# S_ANALOG-G5-5A_schDoc.net
KiCad netlist of a schematic drawn in Altium Designer
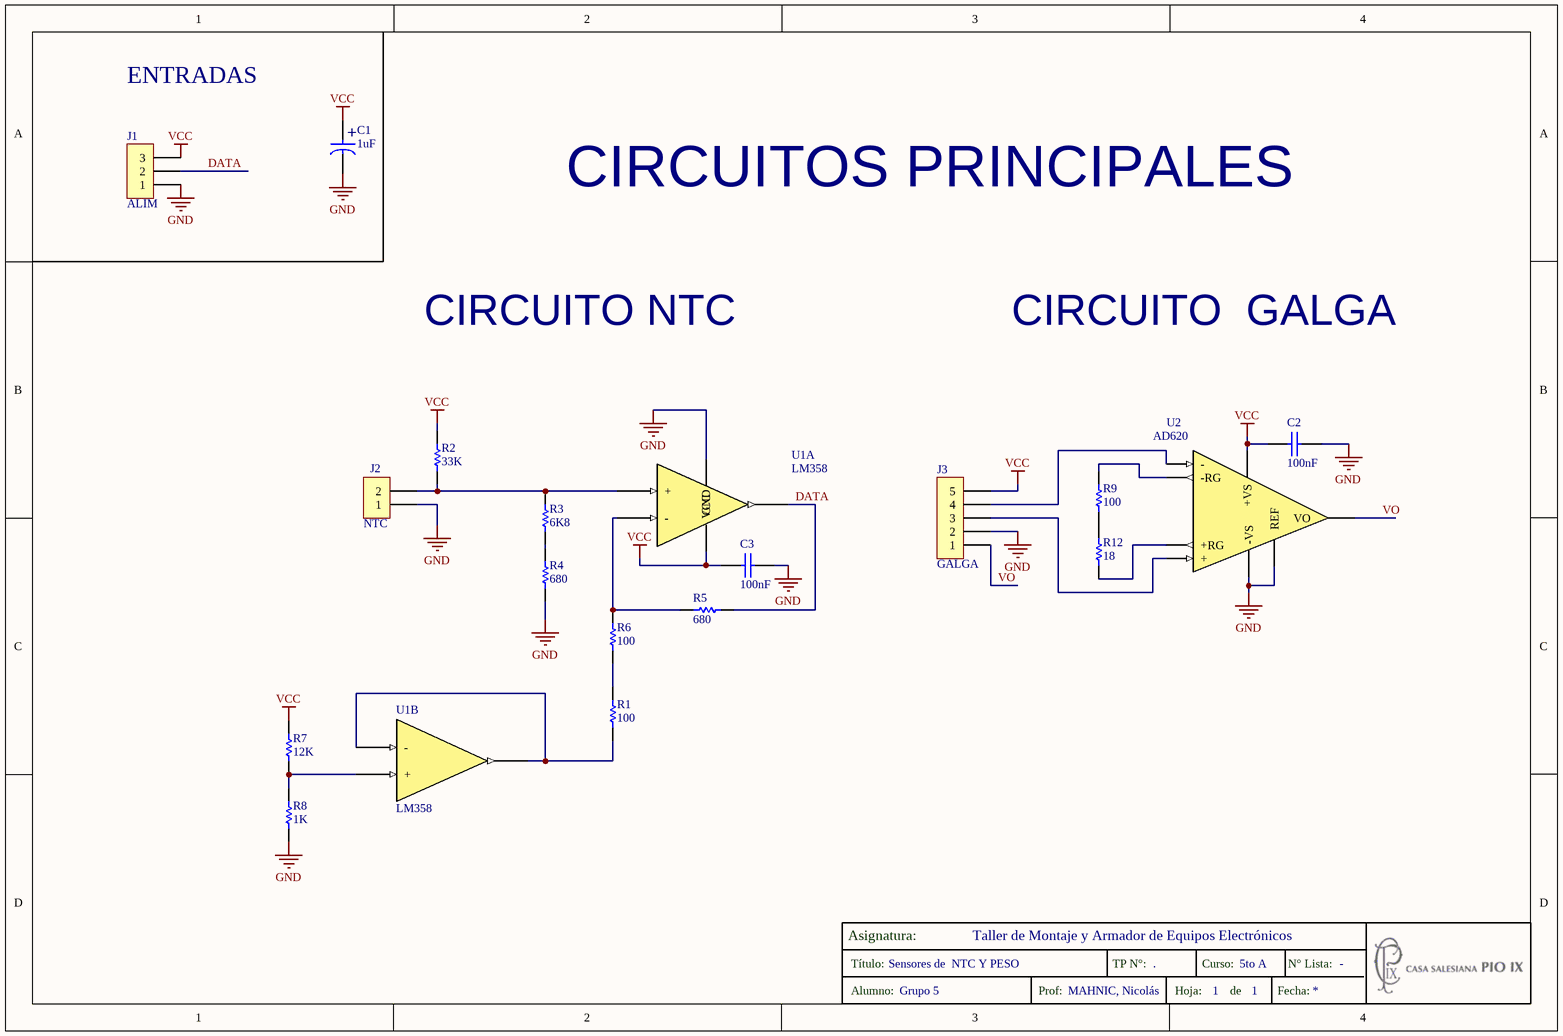
[diagram p0: S.ANALOG-G5-5A.schDoc.SchDoc]

(export (version "E")
  (design (tool "Eeschema 10.0.6"))
  (components
    (comp (ref "C1")
      (value "1uF")
      (footprint "Capol")
      (description "Cap polarizado")
      (libsource (lib "simbolo") (part "CAPPOL"))
    )
    (comp (ref "C2")
      (value "100nF")
      (footprint "0805")
      (description "cap")
      (fields (field (name "AUTOR") "Guido Spataro"))
      (libsource (lib "simbolo") (part "CAP"))
    )
    (comp (ref "C3")
      (value "100nF")
      (footprint "0805")
      (description "cap")
      (fields (field (name "AUTOR") "Guido Spataro"))
      (libsource (lib "simbolo") (part "CAP"))
    )
    (comp (ref "J1") (value "ALIM") (footprint "SIP3") (libsource (lib "simbolo") (part "CON3")))
    (comp (ref "J2") (value "NTC") (footprint "BORNERA2") (libsource (lib "simbolo") (part "BORNERA 2")))
    (comp (ref "J3") (value "GALGA") (footprint "SIP5 90") (libsource (lib "simbolo") (part "CON5")))
    (comp (ref "R1")
      (value "100")
      (footprint "0805")
      (description "Resistencia")
      (fields (field (name "AUTOR") "Guido Spataro"))
      (libsource (lib "simbolo") (part "RES"))
    )
    (comp (ref "R2")
      (value "33K")
      (footprint "0805")
      (description "Resistencia")
      (fields (field (name "AUTOR") "Guido Spataro"))
      (libsource (lib "simbolo") (part "RES"))
    )
    (comp (ref "R3")
      (value "6K8")
      (footprint "0805")
      (description "Resistencia")
      (fields (field (name "AUTOR") "Guido Spataro"))
      (libsource (lib "simbolo") (part "RES"))
    )
    (comp (ref "R4")
      (value "680")
      (footprint "0805")
      (description "Resistencia")
      (fields (field (name "AUTOR") "Guido Spataro"))
      (libsource (lib "simbolo") (part "RES"))
    )
    (comp (ref "R5")
      (value "680")
      (footprint "0805")
      (description "Resistencia")
      (fields (field (name "AUTOR") "Guido Spataro"))
      (libsource (lib "simbolo") (part "RES"))
    )
    (comp (ref "R6")
      (value "100")
      (footprint "0805")
      (description "Resistencia")
      (fields (field (name "AUTOR") "Guido Spataro"))
      (libsource (lib "simbolo") (part "RES"))
    )
    (comp (ref "R7")
      (value "12K")
      (footprint "0805")
      (description "Resistencia")
      (fields (field (name "AUTOR") "Guido Spataro"))
      (libsource (lib "simbolo") (part "RES"))
    )
    (comp (ref "R8")
      (value "1K")
      (footprint "0805")
      (description "Resistencia")
      (fields (field (name "AUTOR") "Guido Spataro"))
      (libsource (lib "simbolo") (part "RES"))
    )
    (comp (ref "R9")
      (value "100")
      (footprint "0805")
      (description "Resistencia")
      (fields (field (name "AUTOR") "Guido Spataro"))
      (libsource (lib "simbolo") (part "RES"))
    )
    (comp (ref "R12")
      (value "18")
      (footprint "0805")
      (description "Resistencia")
      (fields (field (name "AUTOR") "Guido Spataro"))
      (libsource (lib "simbolo") (part "RES"))
    )
    (comp (ref "U1") (value "LM358") (footprint "LM358 SMD") (libsource (lib "simbolo") (part "LM358")))
    (comp (ref "U2") (value "AD620") (footprint "DIP8") (libsource (lib "simbolo") (part "AD623")))
  )
  (nets
    (net (code "1") (name "/DATA") (class "Default")
      (node (ref "J1") (pin "2") (pinfunction "2_2") (pintype "passive"))
      (node (ref "R5") (pin "1") (pinfunction "1_1") (pintype "passive"))
      (node (ref "U1") (pin "1") (pinfunction "OUT_A_1") (pintype "output"))
    )
    (net (code "2") (name "/VO") (class "Default")
      (node (ref "J3") (pin "1") (pinfunction "1_1") (pintype "passive"))
      (node (ref "U2") (pin "6") (pinfunction "VO_6") (pintype "power_in"))
    )
    (net (code "3") (name "GND") (class "Default")
      (node (ref "C1") (pin "2") (pinfunction "2_2") (pintype "passive"))
      (node (ref "C2") (pin "2") (pinfunction "2_2") (pintype "passive"))
      (node (ref "C3") (pin "2") (pinfunction "2_2") (pintype "passive"))
      (node (ref "J1") (pin "1") (pinfunction "1_1") (pintype "passive"))
      (node (ref "J2") (pin "1") (pinfunction "1_1") (pintype "passive"))
      (node (ref "J3") (pin "2") (pinfunction "2_2") (pintype "passive"))
      (node (ref "R4") (pin "1") (pinfunction "1_1") (pintype "passive"))
      (node (ref "R8") (pin "1") (pinfunction "1_1") (pintype "passive"))
      (node (ref "U1") (pin "4") (pinfunction "GND_4") (pintype "passive"))
      (node (ref "U2") (pin "4") (pinfunction "-VS_4") (pintype "passive"))
      (node (ref "U2") (pin "5") (pinfunction "REF_5") (pintype "power_in"))
    )
    (net (code "4") (name "Net-(R1-Pad1)") (class "Default")
      (node (ref "R1") (pin "1") (pinfunction "1_1") (pintype "passive"))
      (node (ref "R6") (pin "2") (pinfunction "2_2") (pintype "passive"))
    )
    (net (code "5") (name "Net-(R3-Pad1)") (class "Default")
      (node (ref "R3") (pin "1") (pinfunction "1_1") (pintype "passive"))
      (node (ref "R4") (pin "2") (pinfunction "2_2") (pintype "passive"))
    )
    (net (code "6") (name "Net-(R12-Pad1)") (class "Default")
      (node (ref "R12") (pin "1") (pinfunction "1_1") (pintype "passive"))
      (node (ref "R9") (pin "2") (pinfunction "2_2") (pintype "passive"))
    )
    (net (code "7") (name "Net-(U1A-+)") (class "Default")
      (node (ref "J2") (pin "2") (pinfunction "2_2") (pintype "passive"))
      (node (ref "R2") (pin "1") (pinfunction "1_1") (pintype "passive"))
      (node (ref "R3") (pin "2") (pinfunction "2_2") (pintype "passive"))
      (node (ref "U1") (pin "3") (pinfunction "+_3") (pintype "input"))
    )
    (net (code "8") (name "Net-(U1A--)") (class "Default")
      (node (ref "R5") (pin "2") (pinfunction "2_2") (pintype "passive"))
      (node (ref "R6") (pin "1") (pinfunction "1_1") (pintype "passive"))
      (node (ref "U1") (pin "2") (pinfunction "-_2") (pintype "input"))
    )
    (net (code "9") (name "Net-(U1B-+)") (class "Default")
      (node (ref "R7") (pin "1") (pinfunction "1_1") (pintype "passive"))
      (node (ref "R8") (pin "2") (pinfunction "2_2") (pintype "passive"))
      (node (ref "U1") (pin "5") (pinfunction "+_5") (pintype "input"))
    )
    (net (code "10") (name "Net-(U1B--)") (class "Default")
      (node (ref "R1") (pin "2") (pinfunction "2_2") (pintype "passive"))
      (node (ref "U1") (pin "6") (pinfunction "-_6") (pintype "input"))
      (node (ref "U1") (pin "7") (pinfunction "OUT_B_7") (pintype "output"))
    )
    (net (code "11") (name "Net-(U2-+)") (class "Default")
      (node (ref "J3") (pin "3") (pinfunction "3_3") (pintype "passive"))
      (node (ref "U2") (pin "3") (pinfunction "+_3") (pintype "input"))
    )
    (net (code "12") (name "Net-(U2-+RG)") (class "Default")
      (node (ref "R12") (pin "2") (pinfunction "2_2") (pintype "passive"))
      (node (ref "U2") (pin "8") (pinfunction "+RG_8") (pintype "output"))
    )
    (net (code "13") (name "Net-(U2--)") (class "Default")
      (node (ref "J3") (pin "4") (pinfunction "4_4") (pintype "passive"))
      (node (ref "U2") (pin "2") (pinfunction "-_2") (pintype "input"))
    )
    (net (code "14") (name "Net-(U2--RG)") (class "Default")
      (node (ref "R9") (pin "1") (pinfunction "1_1") (pintype "passive"))
      (node (ref "U2") (pin "1") (pinfunction "-RG_1") (pintype "output"))
    )
    (net (code "15") (name "VCC") (class "Default")
      (node (ref "C1") (pin "1") (pinfunction "1_1") (pintype "passive"))
      (node (ref "C2") (pin "1") (pinfunction "1_1") (pintype "passive"))
      (node (ref "C3") (pin "1") (pinfunction "1_1") (pintype "passive"))
      (node (ref "J1") (pin "3") (pinfunction "3_3") (pintype "passive"))
      (node (ref "J3") (pin "5") (pinfunction "5_5") (pintype "passive"))
      (node (ref "R2") (pin "2") (pinfunction "2_2") (pintype "passive"))
      (node (ref "R7") (pin "2") (pinfunction "2_2") (pintype "passive"))
      (node (ref "U1") (pin "8") (pinfunction "VCC_8") (pintype "passive"))
      (node (ref "U2") (pin "7") (pinfunction "+VS_7") (pintype "passive"))
    )
  )
)
